# S206X.net
KiCad netlist of a schematic drawn in EAGLE
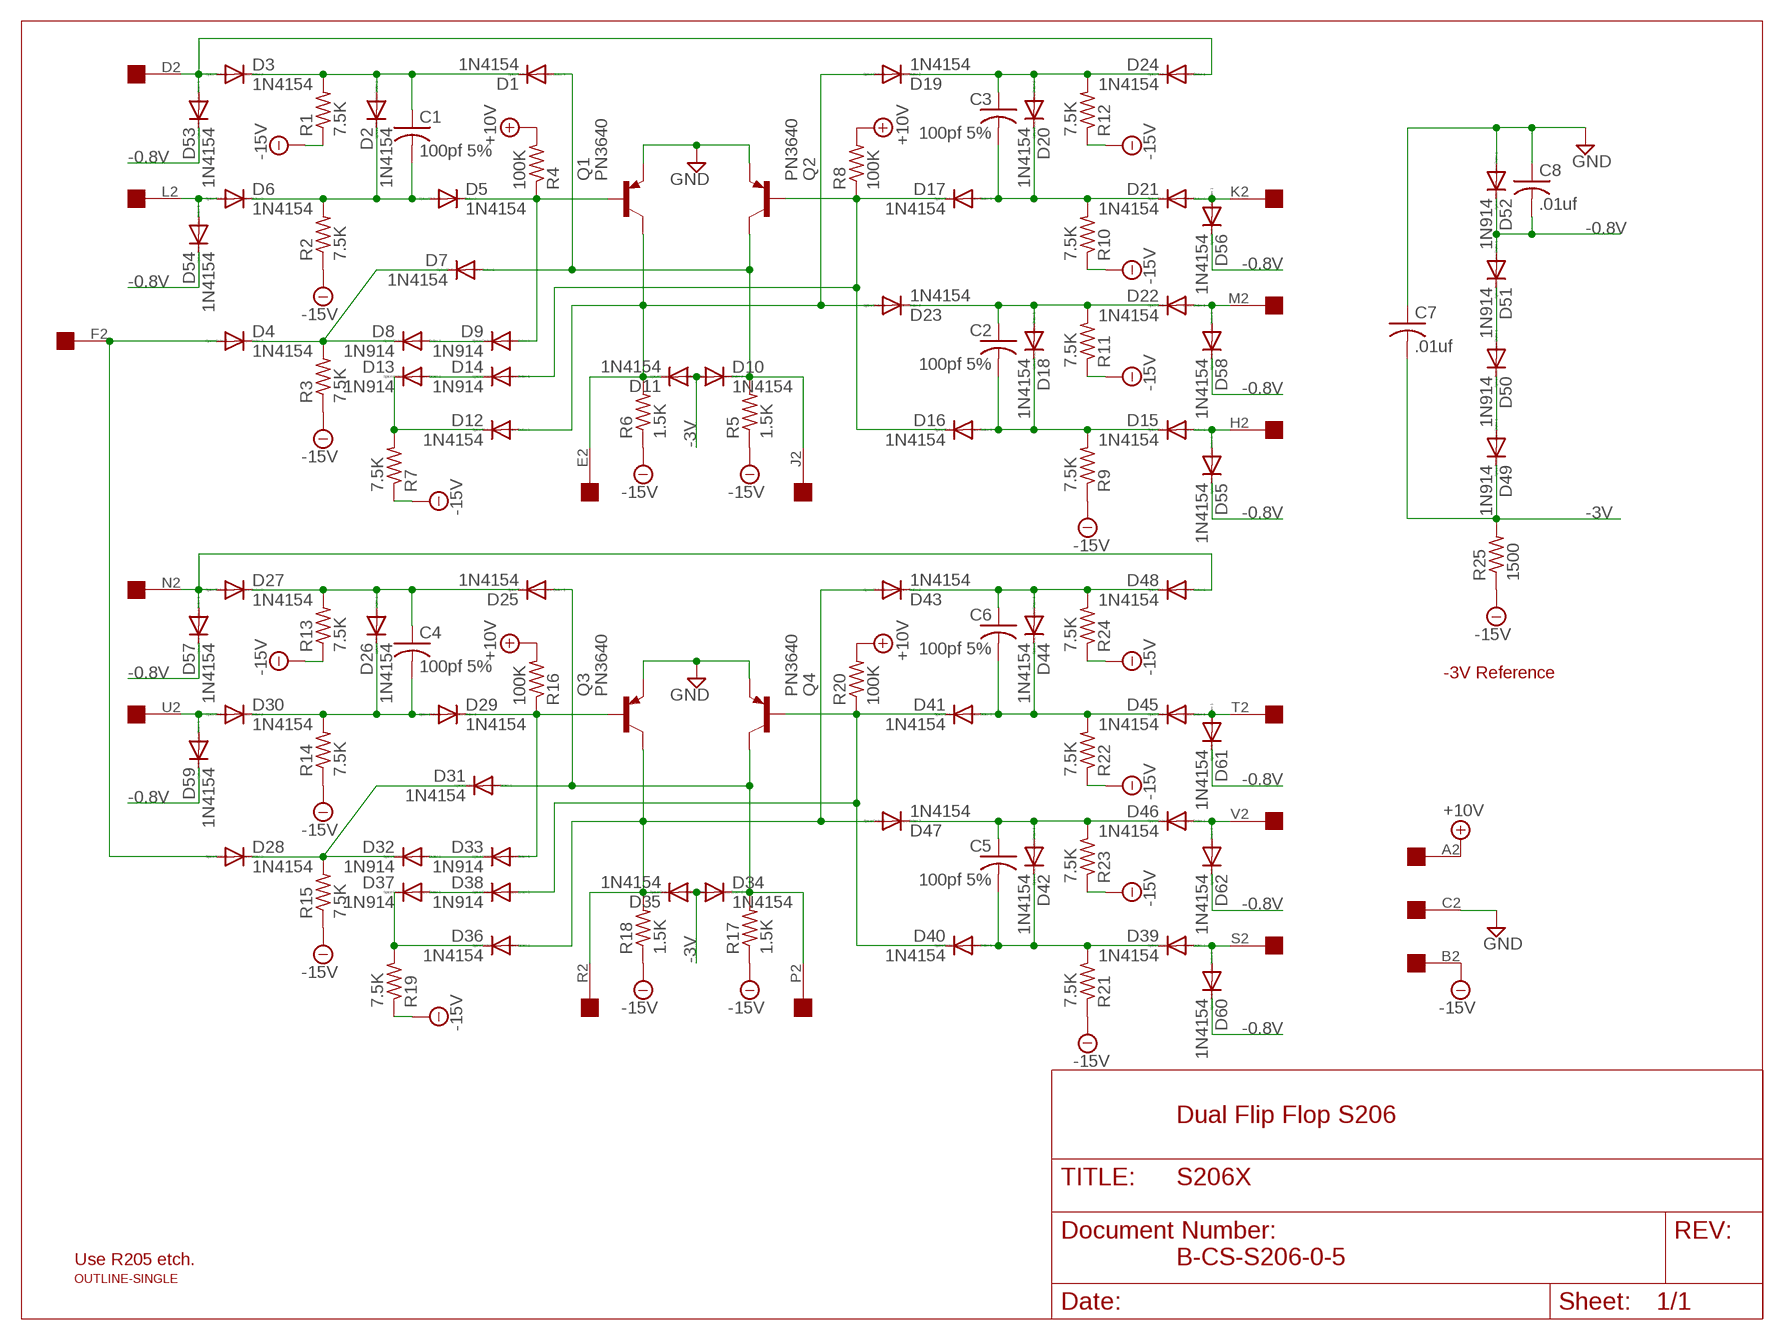
[diagram p0: schematic, sheet 1]

(export (version "E")
  (design (tool "Eeschema 10.0.6"))
  (components
    (comp (ref "C1")
      (value "100pf 5%")
      (footprint "eagle-import:C050-025X075")
      (libsource (lib "eagle-import") (part "C-US050-025X075"))
    )
    (comp (ref "C2")
      (value "100pf 5%")
      (footprint "eagle-import:C050-025X075")
      (libsource (lib "eagle-import") (part "C-US050-025X075"))
    )
    (comp (ref "C3")
      (value "100pf 5%")
      (footprint "eagle-import:C050-025X075")
      (libsource (lib "eagle-import") (part "C-US050-025X075"))
    )
    (comp (ref "C4")
      (value "100pf 5%")
      (footprint "eagle-import:C050-025X075")
      (libsource (lib "eagle-import") (part "C-US050-025X075"))
    )
    (comp (ref "C5")
      (value "100pf 5%")
      (footprint "eagle-import:C050-025X075")
      (libsource (lib "eagle-import") (part "C-US050-025X075"))
    )
    (comp (ref "C6")
      (value "100pf 5%")
      (footprint "eagle-import:C050-025X075")
      (libsource (lib "eagle-import") (part "C-US050-025X075"))
    )
    (comp (ref "C7")
      (value ".01uf")
      (footprint "eagle-import:C050-025X075")
      (libsource (lib "eagle-import") (part "C-US050-025X075"))
    )
    (comp (ref "C8")
      (value ".01uf")
      (footprint "eagle-import:C050-025X075")
      (libsource (lib "eagle-import") (part "C-US050-025X075"))
    )
    (comp (ref "D1")
      (value "1N4154")
      (footprint "eagle-import:DO35-10")
      (libsource (lib "eagle-import") (part "1N4148DO35-10"))
    )
    (comp (ref "D2")
      (value "1N4154")
      (footprint "eagle-import:DO35-10")
      (libsource (lib "eagle-import") (part "1N4148DO35-10"))
    )
    (comp (ref "D3")
      (value "1N4154")
      (footprint "eagle-import:DO35-10")
      (libsource (lib "eagle-import") (part "1N4148DO35-10"))
    )
    (comp (ref "D4")
      (value "1N4154")
      (footprint "eagle-import:DO35-10")
      (libsource (lib "eagle-import") (part "1N4148DO35-10"))
    )
    (comp (ref "D5")
      (value "1N4154")
      (footprint "eagle-import:DO35-10")
      (libsource (lib "eagle-import") (part "1N4148DO35-10"))
    )
    (comp (ref "D6")
      (value "1N4154")
      (footprint "eagle-import:DO35-10")
      (libsource (lib "eagle-import") (part "1N4148DO35-10"))
    )
    (comp (ref "D7")
      (value "1N4154")
      (footprint "eagle-import:DO35-10")
      (libsource (lib "eagle-import") (part "1N4148DO35-10"))
    )
    (comp (ref "D8")
      (value "1N914")
      (footprint "eagle-import:DO35-10")
      (libsource (lib "eagle-import") (part "1N4148DO35-10"))
    )
    (comp (ref "D9")
      (value "1N914")
      (footprint "eagle-import:DO35-10")
      (libsource (lib "eagle-import") (part "1N4148DO35-10"))
    )
    (comp (ref "D10")
      (value "1N4154")
      (footprint "eagle-import:DO35-10")
      (libsource (lib "eagle-import") (part "1N4148DO35-10"))
    )
    (comp (ref "D11")
      (value "1N4154")
      (footprint "eagle-import:DO35-10")
      (libsource (lib "eagle-import") (part "1N4148DO35-10"))
    )
    (comp (ref "D12")
      (value "1N4154")
      (footprint "eagle-import:DO35-10")
      (libsource (lib "eagle-import") (part "1N4148DO35-10"))
    )
    (comp (ref "D13")
      (value "1N914")
      (footprint "eagle-import:DO35-10")
      (libsource (lib "eagle-import") (part "1N4148DO35-10"))
    )
    (comp (ref "D14")
      (value "1N914")
      (footprint "eagle-import:DO35-10")
      (libsource (lib "eagle-import") (part "1N4148DO35-10"))
    )
    (comp (ref "D15")
      (value "1N4154")
      (footprint "eagle-import:DO35-10")
      (libsource (lib "eagle-import") (part "1N4148DO35-10"))
    )
    (comp (ref "D16")
      (value "1N4154")
      (footprint "eagle-import:DO35-10")
      (libsource (lib "eagle-import") (part "1N4148DO35-10"))
    )
    (comp (ref "D17")
      (value "1N4154")
      (footprint "eagle-import:DO35-10")
      (libsource (lib "eagle-import") (part "1N4148DO35-10"))
    )
    (comp (ref "D18")
      (value "1N4154")
      (footprint "eagle-import:DO35-10")
      (libsource (lib "eagle-import") (part "1N4148DO35-10"))
    )
    (comp (ref "D19")
      (value "1N4154")
      (footprint "eagle-import:DO35-10")
      (libsource (lib "eagle-import") (part "1N4148DO35-10"))
    )
    (comp (ref "D20")
      (value "1N4154")
      (footprint "eagle-import:DO35-10")
      (libsource (lib "eagle-import") (part "1N4148DO35-10"))
    )
    (comp (ref "D21")
      (value "1N4154")
      (footprint "eagle-import:DO35-10")
      (libsource (lib "eagle-import") (part "1N4148DO35-10"))
    )
    (comp (ref "D22")
      (value "1N4154")
      (footprint "eagle-import:DO35-10")
      (libsource (lib "eagle-import") (part "1N4148DO35-10"))
    )
    (comp (ref "D23")
      (value "1N4154")
      (footprint "eagle-import:DO35-10")
      (libsource (lib "eagle-import") (part "1N4148DO35-10"))
    )
    (comp (ref "D24")
      (value "1N4154")
      (footprint "eagle-import:DO35-10")
      (libsource (lib "eagle-import") (part "1N4148DO35-10"))
    )
    (comp (ref "D25")
      (value "1N4154")
      (footprint "eagle-import:DO35-10")
      (libsource (lib "eagle-import") (part "1N4148DO35-10"))
    )
    (comp (ref "D26")
      (value "1N4154")
      (footprint "eagle-import:DO35-10")
      (libsource (lib "eagle-import") (part "1N4148DO35-10"))
    )
    (comp (ref "D27")
      (value "1N4154")
      (footprint "eagle-import:DO35-10")
      (libsource (lib "eagle-import") (part "1N4148DO35-10"))
    )
    (comp (ref "D28")
      (value "1N4154")
      (footprint "eagle-import:DO35-10")
      (libsource (lib "eagle-import") (part "1N4148DO35-10"))
    )
    (comp (ref "D29")
      (value "1N4154")
      (footprint "eagle-import:DO35-10")
      (libsource (lib "eagle-import") (part "1N4148DO35-10"))
    )
    (comp (ref "D30")
      (value "1N4154")
      (footprint "eagle-import:DO35-10")
      (libsource (lib "eagle-import") (part "1N4148DO35-10"))
    )
    (comp (ref "D31")
      (value "1N4154")
      (footprint "eagle-import:DO35-10")
      (libsource (lib "eagle-import") (part "1N4148DO35-10"))
    )
    (comp (ref "D32")
      (value "1N914")
      (footprint "eagle-import:DO35-10")
      (libsource (lib "eagle-import") (part "1N4148DO35-10"))
    )
    (comp (ref "D33")
      (value "1N914")
      (footprint "eagle-import:DO35-10")
      (libsource (lib "eagle-import") (part "1N4148DO35-10"))
    )
    (comp (ref "D34")
      (value "1N4154")
      (footprint "eagle-import:DO35-10")
      (libsource (lib "eagle-import") (part "1N4148DO35-10"))
    )
    (comp (ref "D35")
      (value "1N4154")
      (footprint "eagle-import:DO35-10")
      (libsource (lib "eagle-import") (part "1N4148DO35-10"))
    )
    (comp (ref "D36")
      (value "1N4154")
      (footprint "eagle-import:DO35-10")
      (libsource (lib "eagle-import") (part "1N4148DO35-10"))
    )
    (comp (ref "D37")
      (value "1N914")
      (footprint "eagle-import:DO35-10")
      (libsource (lib "eagle-import") (part "1N4148DO35-10"))
    )
    (comp (ref "D38")
      (value "1N914")
      (footprint "eagle-import:DO35-10")
      (libsource (lib "eagle-import") (part "1N4148DO35-10"))
    )
    (comp (ref "D39")
      (value "1N4154")
      (footprint "eagle-import:DO35-10")
      (libsource (lib "eagle-import") (part "1N4148DO35-10"))
    )
    (comp (ref "D40")
      (value "1N4154")
      (footprint "eagle-import:DO35-10")
      (libsource (lib "eagle-import") (part "1N4148DO35-10"))
    )
    (comp (ref "D41")
      (value "1N4154")
      (footprint "eagle-import:DO35-10")
      (libsource (lib "eagle-import") (part "1N4148DO35-10"))
    )
    (comp (ref "D42")
      (value "1N4154")
      (footprint "eagle-import:DO35-10")
      (libsource (lib "eagle-import") (part "1N4148DO35-10"))
    )
    (comp (ref "D43")
      (value "1N4154")
      (footprint "eagle-import:DO35-10")
      (libsource (lib "eagle-import") (part "1N4148DO35-10"))
    )
    (comp (ref "D44")
      (value "1N4154")
      (footprint "eagle-import:DO35-10")
      (libsource (lib "eagle-import") (part "1N4148DO35-10"))
    )
    (comp (ref "D45")
      (value "1N4154")
      (footprint "eagle-import:DO35-10")
      (libsource (lib "eagle-import") (part "1N4148DO35-10"))
    )
    (comp (ref "D46")
      (value "1N4154")
      (footprint "eagle-import:DO35-10")
      (libsource (lib "eagle-import") (part "1N4148DO35-10"))
    )
    (comp (ref "D47")
      (value "1N4154")
      (footprint "eagle-import:DO35-10")
      (libsource (lib "eagle-import") (part "1N4148DO35-10"))
    )
    (comp (ref "D48")
      (value "1N4154")
      (footprint "eagle-import:DO35-10")
      (libsource (lib "eagle-import") (part "1N4148DO35-10"))
    )
    (comp (ref "D49")
      (value "1N914")
      (footprint "eagle-import:DO35-10")
      (libsource (lib "eagle-import") (part "1N4148DO35-10"))
    )
    (comp (ref "D50")
      (value "1N914")
      (footprint "eagle-import:DO35-10")
      (libsource (lib "eagle-import") (part "1N4148DO35-10"))
    )
    (comp (ref "D51")
      (value "1N914")
      (footprint "eagle-import:DO35-10")
      (libsource (lib "eagle-import") (part "1N4148DO35-10"))
    )
    (comp (ref "D52")
      (value "1N914")
      (footprint "eagle-import:DO35-10")
      (libsource (lib "eagle-import") (part "1N4148DO35-10"))
    )
    (comp (ref "D53")
      (value "1N4154")
      (footprint "eagle-import:DO35-10")
      (libsource (lib "eagle-import") (part "1N4148DO35-10"))
    )
    (comp (ref "D54")
      (value "1N4154")
      (footprint "eagle-import:DO35-10")
      (libsource (lib "eagle-import") (part "1N4148DO35-10"))
    )
    (comp (ref "D55")
      (value "1N4154")
      (footprint "eagle-import:DO35-10")
      (libsource (lib "eagle-import") (part "1N4148DO35-10"))
    )
    (comp (ref "D56")
      (value "1N4154")
      (footprint "eagle-import:DO35-10")
      (libsource (lib "eagle-import") (part "1N4148DO35-10"))
    )
    (comp (ref "D57")
      (value "1N4154")
      (footprint "eagle-import:DO35-10")
      (libsource (lib "eagle-import") (part "1N4148DO35-10"))
    )
    (comp (ref "D58")
      (value "1N4154")
      (footprint "eagle-import:DO35-10")
      (libsource (lib "eagle-import") (part "1N4148DO35-10"))
    )
    (comp (ref "D59")
      (value "1N4154")
      (footprint "eagle-import:DO35-10")
      (libsource (lib "eagle-import") (part "1N4148DO35-10"))
    )
    (comp (ref "D60")
      (value "1N4154")
      (footprint "eagle-import:DO35-10")
      (libsource (lib "eagle-import") (part "1N4148DO35-10"))
    )
    (comp (ref "D61")
      (value "1N4154")
      (footprint "eagle-import:DO35-10")
      (libsource (lib "eagle-import") (part "1N4148DO35-10"))
    )
    (comp (ref "D62")
      (value "1N4154")
      (footprint "eagle-import:DO35-10")
      (libsource (lib "eagle-import") (part "1N4148DO35-10"))
    )
    (comp (ref "Q1")
      (value "PN3640")
      (footprint "eagle-import:TO39")
      (libsource (lib "eagle-import") (part "2N3637"))
    )
    (comp (ref "Q2")
      (value "PN3640")
      (footprint "eagle-import:TO39")
      (libsource (lib "eagle-import") (part "2N3637"))
    )
    (comp (ref "Q3")
      (value "PN3640")
      (footprint "eagle-import:TO39")
      (libsource (lib "eagle-import") (part "2N3637"))
    )
    (comp (ref "Q4")
      (value "PN3640")
      (footprint "eagle-import:TO39")
      (libsource (lib "eagle-import") (part "2N3637"))
    )
    (comp (ref "R1")
      (value "7.5K")
      (footprint "eagle-import:0207_10")
      (libsource (lib "eagle-import") (part "R-US_0207/10"))
    )
    (comp (ref "R2")
      (value "7.5K")
      (footprint "eagle-import:0207_10")
      (libsource (lib "eagle-import") (part "R-US_0207/10"))
    )
    (comp (ref "R3")
      (value "7.5K")
      (footprint "eagle-import:0207_10")
      (libsource (lib "eagle-import") (part "R-US_0207/10"))
    )
    (comp (ref "R4")
      (value "100K")
      (footprint "eagle-import:0207_10")
      (libsource (lib "eagle-import") (part "R-US_0207/10"))
    )
    (comp (ref "R5")
      (value "1.5K")
      (footprint "eagle-import:0207_10")
      (libsource (lib "eagle-import") (part "R-US_0207/10"))
    )
    (comp (ref "R6")
      (value "1.5K")
      (footprint "eagle-import:0207_10")
      (libsource (lib "eagle-import") (part "R-US_0207/10"))
    )
    (comp (ref "R7")
      (value "7.5K")
      (footprint "eagle-import:0207_10")
      (libsource (lib "eagle-import") (part "R-US_0207/10"))
    )
    (comp (ref "R8")
      (value "100K")
      (footprint "eagle-import:0207_10")
      (libsource (lib "eagle-import") (part "R-US_0207/10"))
    )
    (comp (ref "R9")
      (value "7.5K")
      (footprint "eagle-import:0207_10")
      (libsource (lib "eagle-import") (part "R-US_0207/10"))
    )
    (comp (ref "R10")
      (value "7.5K")
      (footprint "eagle-import:0207_10")
      (libsource (lib "eagle-import") (part "R-US_0207/10"))
    )
    (comp (ref "R11")
      (value "7.5K")
      (footprint "eagle-import:0207_10")
      (libsource (lib "eagle-import") (part "R-US_0207/10"))
    )
    (comp (ref "R12")
      (value "7.5K")
      (footprint "eagle-import:0207_10")
      (libsource (lib "eagle-import") (part "R-US_0207/10"))
    )
    (comp (ref "R13")
      (value "7.5K")
      (footprint "eagle-import:0207_10")
      (libsource (lib "eagle-import") (part "R-US_0207/10"))
    )
    (comp (ref "R14")
      (value "7.5K")
      (footprint "eagle-import:0207_10")
      (libsource (lib "eagle-import") (part "R-US_0207/10"))
    )
    (comp (ref "R15")
      (value "7.5K")
      (footprint "eagle-import:0207_10")
      (libsource (lib "eagle-import") (part "R-US_0207/10"))
    )
    (comp (ref "R16")
      (value "100K")
      (footprint "eagle-import:0207_10")
      (libsource (lib "eagle-import") (part "R-US_0207/10"))
    )
    (comp (ref "R17")
      (value "1.5K")
      (footprint "eagle-import:0207_10")
      (libsource (lib "eagle-import") (part "R-US_0207/10"))
    )
    (comp (ref "R18")
      (value "1.5K")
      (footprint "eagle-import:0207_10")
      (libsource (lib "eagle-import") (part "R-US_0207/10"))
    )
    (comp (ref "R19")
      (value "7.5K")
      (footprint "eagle-import:0207_10")
      (libsource (lib "eagle-import") (part "R-US_0207/10"))
    )
    (comp (ref "R20")
      (value "100K")
      (footprint "eagle-import:0207_10")
      (libsource (lib "eagle-import") (part "R-US_0207/10"))
    )
    (comp (ref "R21")
      (value "7.5K")
      (footprint "eagle-import:0207_10")
      (libsource (lib "eagle-import") (part "R-US_0207/10"))
    )
    (comp (ref "R22")
      (value "7.5K")
      (footprint "eagle-import:0207_10")
      (libsource (lib "eagle-import") (part "R-US_0207/10"))
    )
    (comp (ref "R23")
      (value "7.5K")
      (footprint "eagle-import:0207_10")
      (libsource (lib "eagle-import") (part "R-US_0207/10"))
    )
    (comp (ref "R24")
      (value "7.5K")
      (footprint "eagle-import:0207_10")
      (libsource (lib "eagle-import") (part "R-US_0207/10"))
    )
    (comp (ref "R25")
      (value "1500")
      (footprint "eagle-import:0207_10")
      (libsource (lib "eagle-import") (part "R-US_0207/10"))
    )
    (comp (ref "U$1")
      (value "OUTLINE-SINGLE")
      (footprint "eagle-import:SINGLE")
      (libsource (lib "eagle-import") (part "OUTLINE-SINGLE"))
    )
    (comp (ref "U$2")
      (value "EDGE-1")
      (footprint "eagle-import:EDGE-CON1")
      (libsource (lib "eagle-import") (part "EDGE-1"))
    )
  )
  (nets
    (net (code "1") (name "+10V") (class "Default")
      (node (ref "R16") (pin "2") (pinfunction "2_2") (pintype "passive"))
      (node (ref "R20") (pin "2") (pinfunction "2_2") (pintype "passive"))
      (node (ref "R4") (pin "2") (pinfunction "2_2") (pintype "passive"))
      (node (ref "R8") (pin "2") (pinfunction "2_2") (pintype "passive"))
      (node (ref "U$2") (pin "A2") (pinfunction "1_A2") (pintype "bidirectional"))
    )
    (net (code "2") (name "-15V") (class "Default")
      (node (ref "R1") (pin "1") (pinfunction "1_1") (pintype "passive"))
      (node (ref "R10") (pin "1") (pinfunction "1_1") (pintype "passive"))
      (node (ref "R11") (pin "1") (pinfunction "1_1") (pintype "passive"))
      (node (ref "R12") (pin "1") (pinfunction "1_1") (pintype "passive"))
      (node (ref "R13") (pin "1") (pinfunction "1_1") (pintype "passive"))
      (node (ref "R14") (pin "1") (pinfunction "1_1") (pintype "passive"))
      (node (ref "R15") (pin "1") (pinfunction "1_1") (pintype "passive"))
      (node (ref "R17") (pin "1") (pinfunction "1_1") (pintype "passive"))
      (node (ref "R18") (pin "1") (pinfunction "1_1") (pintype "passive"))
      (node (ref "R19") (pin "1") (pinfunction "1_1") (pintype "passive"))
      (node (ref "R2") (pin "1") (pinfunction "1_1") (pintype "passive"))
      (node (ref "R21") (pin "1") (pinfunction "1_1") (pintype "passive"))
      (node (ref "R22") (pin "1") (pinfunction "1_1") (pintype "passive"))
      (node (ref "R23") (pin "1") (pinfunction "1_1") (pintype "passive"))
      (node (ref "R24") (pin "1") (pinfunction "1_1") (pintype "passive"))
      (node (ref "R25") (pin "1") (pinfunction "1_1") (pintype "passive"))
      (node (ref "R3") (pin "1") (pinfunction "1_1") (pintype "passive"))
      (node (ref "R5") (pin "1") (pinfunction "1_1") (pintype "passive"))
      (node (ref "R6") (pin "1") (pinfunction "1_1") (pintype "passive"))
      (node (ref "R7") (pin "1") (pinfunction "1_1") (pintype "passive"))
      (node (ref "R9") (pin "1") (pinfunction "1_1") (pintype "passive"))
      (node (ref "U$2") (pin "B2") (pinfunction "1_B2") (pintype "bidirectional"))
    )
    (net (code "3") (name "/-0.8V") (class "Default")
      (node (ref "C8") (pin "2") (pinfunction "2_2") (pintype "passive"))
      (node (ref "D51") (pin "A") (pinfunction "A_A") (pintype "passive"))
      (node (ref "D52") (pin "C") (pinfunction "C_C") (pintype "passive"))
      (node (ref "D53") (pin "C") (pinfunction "C_C") (pintype "passive"))
      (node (ref "D54") (pin "C") (pinfunction "C_C") (pintype "passive"))
      (node (ref "D55") (pin "C") (pinfunction "C_C") (pintype "passive"))
      (node (ref "D56") (pin "C") (pinfunction "C_C") (pintype "passive"))
      (node (ref "D57") (pin "C") (pinfunction "C_C") (pintype "passive"))
      (node (ref "D58") (pin "C") (pinfunction "C_C") (pintype "passive"))
      (node (ref "D59") (pin "C") (pinfunction "C_C") (pintype "passive"))
      (node (ref "D60") (pin "C") (pinfunction "C_C") (pintype "passive"))
      (node (ref "D61") (pin "C") (pinfunction "C_C") (pintype "passive"))
      (node (ref "D62") (pin "C") (pinfunction "C_C") (pintype "passive"))
    )
    (net (code "4") (name "/-3V") (class "Default")
      (node (ref "C7") (pin "2") (pinfunction "2_2") (pintype "passive"))
      (node (ref "D10") (pin "A") (pinfunction "A_A") (pintype "passive"))
      (node (ref "D11") (pin "A") (pinfunction "A_A") (pintype "passive"))
      (node (ref "D34") (pin "A") (pinfunction "A_A") (pintype "passive"))
      (node (ref "D35") (pin "A") (pinfunction "A_A") (pintype "passive"))
      (node (ref "D49") (pin "C") (pinfunction "C_C") (pintype "passive"))
      (node (ref "R25") (pin "2") (pinfunction "2_2") (pintype "passive"))
    )
    (net (code "5") (name "GND") (class "Default")
      (node (ref "C7") (pin "1") (pinfunction "1_1") (pintype "passive"))
      (node (ref "C8") (pin "1") (pinfunction "1_1") (pintype "passive"))
      (node (ref "D52") (pin "A") (pinfunction "A_A") (pintype "passive"))
      (node (ref "Q1") (pin "1") (pinfunction "E_1") (pintype "passive"))
      (node (ref "Q2") (pin "1") (pinfunction "E_1") (pintype "passive"))
      (node (ref "Q3") (pin "1") (pinfunction "E_1") (pintype "passive"))
      (node (ref "Q4") (pin "1") (pinfunction "E_1") (pintype "passive"))
      (node (ref "U$2") (pin "C2") (pinfunction "1_C2") (pintype "bidirectional"))
    )
    (net (code "6") (name "Net-(C1-Pad1)") (class "Default")
      (node (ref "C1") (pin "1") (pinfunction "1_1") (pintype "passive"))
      (node (ref "D1") (pin "C") (pinfunction "C_C") (pintype "passive"))
      (node (ref "D2") (pin "A") (pinfunction "A_A") (pintype "passive"))
      (node (ref "D3") (pin "C") (pinfunction "C_C") (pintype "passive"))
      (node (ref "R1") (pin "2") (pinfunction "2_2") (pintype "passive"))
    )
    (net (code "7") (name "Net-(C1-Pad2)") (class "Default")
      (node (ref "C1") (pin "2") (pinfunction "2_2") (pintype "passive"))
      (node (ref "D2") (pin "C") (pinfunction "C_C") (pintype "passive"))
      (node (ref "D5") (pin "A") (pinfunction "A_A") (pintype "passive"))
      (node (ref "D6") (pin "C") (pinfunction "C_C") (pintype "passive"))
      (node (ref "R2") (pin "2") (pinfunction "2_2") (pintype "passive"))
    )
    (net (code "8") (name "Net-(C2-Pad1)") (class "Default")
      (node (ref "C2") (pin "1") (pinfunction "1_1") (pintype "passive"))
      (node (ref "D18") (pin "A") (pinfunction "A_A") (pintype "passive"))
      (node (ref "D22") (pin "C") (pinfunction "C_C") (pintype "passive"))
      (node (ref "D23") (pin "C") (pinfunction "C_C") (pintype "passive"))
      (node (ref "R11") (pin "2") (pinfunction "2_2") (pintype "passive"))
    )
    (net (code "9") (name "Net-(C2-Pad2)") (class "Default")
      (node (ref "C2") (pin "2") (pinfunction "2_2") (pintype "passive"))
      (node (ref "D15") (pin "C") (pinfunction "C_C") (pintype "passive"))
      (node (ref "D16") (pin "A") (pinfunction "A_A") (pintype "passive"))
      (node (ref "D18") (pin "C") (pinfunction "C_C") (pintype "passive"))
      (node (ref "R9") (pin "2") (pinfunction "2_2") (pintype "passive"))
    )
    (net (code "10") (name "Net-(C3-Pad1)") (class "Default")
      (node (ref "C3") (pin "1") (pinfunction "1_1") (pintype "passive"))
      (node (ref "D19") (pin "C") (pinfunction "C_C") (pintype "passive"))
      (node (ref "D20") (pin "A") (pinfunction "A_A") (pintype "passive"))
      (node (ref "D24") (pin "C") (pinfunction "C_C") (pintype "passive"))
      (node (ref "R12") (pin "2") (pinfunction "2_2") (pintype "passive"))
    )
    (net (code "11") (name "Net-(C3-Pad2)") (class "Default")
      (node (ref "C3") (pin "2") (pinfunction "2_2") (pintype "passive"))
      (node (ref "D17") (pin "A") (pinfunction "A_A") (pintype "passive"))
      (node (ref "D20") (pin "C") (pinfunction "C_C") (pintype "passive"))
      (node (ref "D21") (pin "C") (pinfunction "C_C") (pintype "passive"))
      (node (ref "R10") (pin "2") (pinfunction "2_2") (pintype "passive"))
    )
    (net (code "12") (name "Net-(C4-Pad1)") (class "Default")
      (node (ref "C4") (pin "1") (pinfunction "1_1") (pintype "passive"))
      (node (ref "D25") (pin "C") (pinfunction "C_C") (pintype "passive"))
      (node (ref "D26") (pin "A") (pinfunction "A_A") (pintype "passive"))
      (node (ref "D27") (pin "C") (pinfunction "C_C") (pintype "passive"))
      (node (ref "R13") (pin "2") (pinfunction "2_2") (pintype "passive"))
    )
    (net (code "13") (name "Net-(C4-Pad2)") (class "Default")
      (node (ref "C4") (pin "2") (pinfunction "2_2") (pintype "passive"))
      (node (ref "D26") (pin "C") (pinfunction "C_C") (pintype "passive"))
      (node (ref "D29") (pin "A") (pinfunction "A_A") (pintype "passive"))
      (node (ref "D30") (pin "C") (pinfunction "C_C") (pintype "passive"))
      (node (ref "R14") (pin "2") (pinfunction "2_2") (pintype "passive"))
    )
    (net (code "14") (name "Net-(C5-Pad1)") (class "Default")
      (node (ref "C5") (pin "1") (pinfunction "1_1") (pintype "passive"))
      (node (ref "D42") (pin "A") (pinfunction "A_A") (pintype "passive"))
      (node (ref "D46") (pin "C") (pinfunction "C_C") (pintype "passive"))
      (node (ref "D47") (pin "C") (pinfunction "C_C") (pintype "passive"))
      (node (ref "R23") (pin "2") (pinfunction "2_2") (pintype "passive"))
    )
    (net (code "15") (name "Net-(C5-Pad2)") (class "Default")
      (node (ref "C5") (pin "2") (pinfunction "2_2") (pintype "passive"))
      (node (ref "D39") (pin "C") (pinfunction "C_C") (pintype "passive"))
      (node (ref "D40") (pin "A") (pinfunction "A_A") (pintype "passive"))
      (node (ref "D42") (pin "C") (pinfunction "C_C") (pintype "passive"))
      (node (ref "R21") (pin "2") (pinfunction "2_2") (pintype "passive"))
    )
    (net (code "16") (name "Net-(C6-Pad1)") (class "Default")
      (node (ref "C6") (pin "1") (pinfunction "1_1") (pintype "passive"))
      (node (ref "D43") (pin "C") (pinfunction "C_C") (pintype "passive"))
      (node (ref "D44") (pin "A") (pinfunction "A_A") (pintype "passive"))
      (node (ref "D48") (pin "C") (pinfunction "C_C") (pintype "passive"))
      (node (ref "R24") (pin "2") (pinfunction "2_2") (pintype "passive"))
    )
    (net (code "17") (name "Net-(C6-Pad2)") (class "Default")
      (node (ref "C6") (pin "2") (pinfunction "2_2") (pintype "passive"))
      (node (ref "D41") (pin "A") (pinfunction "A_A") (pintype "passive"))
      (node (ref "D44") (pin "C") (pinfunction "C_C") (pintype "passive"))
      (node (ref "D45") (pin "C") (pinfunction "C_C") (pintype "passive"))
      (node (ref "R22") (pin "2") (pinfunction "2_2") (pintype "passive"))
    )
    (net (code "18") (name "Net-(D4-PadC)") (class "Default")
      (node (ref "D4") (pin "C") (pinfunction "C_C") (pintype "passive"))
      (node (ref "D7") (pin "C") (pinfunction "C_C") (pintype "passive"))
      (node (ref "D8") (pin "C") (pinfunction "C_C") (pintype "passive"))
      (node (ref "R3") (pin "2") (pinfunction "2_2") (pintype "passive"))
    )
    (net (code "19") (name "Net-(D8-PadA)") (class "Default")
      (node (ref "D8") (pin "A") (pinfunction "A_A") (pintype "passive"))
      (node (ref "D9") (pin "C") (pinfunction "C_C") (pintype "passive"))
    )
    (net (code "20") (name "Net-(D12-PadC)") (class "Default")
      (node (ref "D12") (pin "C") (pinfunction "C_C") (pintype "passive"))
      (node (ref "D13") (pin "C") (pinfunction "C_C") (pintype "passive"))
      (node (ref "R7") (pin "2") (pinfunction "2_2") (pintype "passive"))
    )
    (net (code "21") (name "Net-(D13-PadA)") (class "Default")
      (node (ref "D13") (pin "A") (pinfunction "A_A") (pintype "passive"))
      (node (ref "D14") (pin "C") (pinfunction "C_C") (pintype "passive"))
    )
    (net (code "22") (name "Net-(D28-PadC)") (class "Default")
      (node (ref "D28") (pin "C") (pinfunction "C_C") (pintype "passive"))
      (node (ref "D31") (pin "C") (pinfunction "C_C") (pintype "passive"))
      (node (ref "D32") (pin "C") (pinfunction "C_C") (pintype "passive"))
      (node (ref "R15") (pin "2") (pinfunction "2_2") (pintype "passive"))
    )
    (net (code "23") (name "Net-(D32-PadA)") (class "Default")
      (node (ref "D32") (pin "A") (pinfunction "A_A") (pintype "passive"))
      (node (ref "D33") (pin "C") (pinfunction "C_C") (pintype "passive"))
    )
    (net (code "24") (name "Net-(D36-PadC)") (class "Default")
      (node (ref "D36") (pin "C") (pinfunction "C_C") (pintype "passive"))
      (node (ref "D37") (pin "C") (pinfunction "C_C") (pintype "passive"))
      (node (ref "R19") (pin "2") (pinfunction "2_2") (pintype "passive"))
    )
    (net (code "25") (name "Net-(D37-PadA)") (class "Default")
      (node (ref "D37") (pin "A") (pinfunction "A_A") (pintype "passive"))
      (node (ref "D38") (pin "C") (pinfunction "C_C") (pintype "passive"))
    )
    (net (code "26") (name "Net-(D49-PadA)") (class "Default")
      (node (ref "D49") (pin "A") (pinfunction "A_A") (pintype "passive"))
      (node (ref "D50") (pin "C") (pinfunction "C_C") (pintype "passive"))
    )
    (net (code "27") (name "Net-(D50-PadA)") (class "Default")
      (node (ref "D50") (pin "A") (pinfunction "A_A") (pintype "passive"))
      (node (ref "D51") (pin "C") (pinfunction "C_C") (pintype "passive"))
    )
    (net (code "28") (name "Net-(Q1-B)") (class "Default")
      (node (ref "D5") (pin "C") (pinfunction "C_C") (pintype "passive"))
      (node (ref "D9") (pin "A") (pinfunction "A_A") (pintype "passive"))
      (node (ref "Q1") (pin "2") (pinfunction "B_2") (pintype "passive"))
      (node (ref "R4") (pin "1") (pinfunction "1_1") (pintype "passive"))
    )
    (net (code "29") (name "Net-(Q1-C)") (class "Default")
      (node (ref "D11") (pin "C") (pinfunction "C_C") (pintype "passive"))
      (node (ref "D12") (pin "A") (pinfunction "A_A") (pintype "passive"))
      (node (ref "D19") (pin "A") (pinfunction "A_A") (pintype "passive"))
      (node (ref "D23") (pin "A") (pinfunction "A_A") (pintype "passive"))
      (node (ref "Q1") (pin "3") (pinfunction "C_3") (pintype "passive"))
      (node (ref "R6") (pin "2") (pinfunction "2_2") (pintype "passive"))
      (node (ref "U$2") (pin "E2") (pinfunction "1_E2") (pintype "bidirectional"))
    )
    (net (code "30") (name "Net-(Q2-B)") (class "Default")
      (node (ref "D14") (pin "A") (pinfunction "A_A") (pintype "passive"))
      (node (ref "D16") (pin "C") (pinfunction "C_C") (pintype "passive"))
      (node (ref "D17") (pin "C") (pinfunction "C_C") (pintype "passive"))
      (node (ref "Q2") (pin "2") (pinfunction "B_2") (pintype "passive"))
      (node (ref "R8") (pin "1") (pinfunction "1_1") (pintype "passive"))
    )
    (net (code "31") (name "Net-(Q2-C)") (class "Default")
      (node (ref "D1") (pin "A") (pinfunction "A_A") (pintype "passive"))
      (node (ref "D10") (pin "C") (pinfunction "C_C") (pintype "passive"))
      (node (ref "D7") (pin "A") (pinfunction "A_A") (pintype "passive"))
      (node (ref "Q2") (pin "3") (pinfunction "C_3") (pintype "passive"))
      (node (ref "R5") (pin "2") (pinfunction "2_2") (pintype "passive"))
      (node (ref "U$2") (pin "J2") (pinfunction "1_J2") (pintype "bidirectional"))
    )
    (net (code "32") (name "Net-(Q3-B)") (class "Default")
      (node (ref "D29") (pin "C") (pinfunction "C_C") (pintype "passive"))
      (node (ref "D33") (pin "A") (pinfunction "A_A") (pintype "passive"))
      (node (ref "Q3") (pin "2") (pinfunction "B_2") (pintype "passive"))
      (node (ref "R16") (pin "1") (pinfunction "1_1") (pintype "passive"))
    )
    (net (code "33") (name "Net-(Q3-C)") (class "Default")
      (node (ref "D35") (pin "C") (pinfunction "C_C") (pintype "passive"))
      (node (ref "D36") (pin "A") (pinfunction "A_A") (pintype "passive"))
      (node (ref "D43") (pin "A") (pinfunction "A_A") (pintype "passive"))
      (node (ref "D47") (pin "A") (pinfunction "A_A") (pintype "passive"))
      (node (ref "Q3") (pin "3") (pinfunction "C_3") (pintype "passive"))
      (node (ref "R18") (pin "2") (pinfunction "2_2") (pintype "passive"))
      (node (ref "U$2") (pin "R2") (pinfunction "1_R2") (pintype "bidirectional"))
    )
    (net (code "34") (name "Net-(Q4-B)") (class "Default")
      (node (ref "D38") (pin "A") (pinfunction "A_A") (pintype "passive"))
      (node (ref "D40") (pin "C") (pinfunction "C_C") (pintype "passive"))
      (node (ref "D41") (pin "C") (pinfunction "C_C") (pintype "passive"))
      (node (ref "Q4") (pin "2") (pinfunction "B_2") (pintype "passive"))
      (node (ref "R20") (pin "1") (pinfunction "1_1") (pintype "passive"))
    )
    (net (code "35") (name "Net-(Q4-C)") (class "Default")
      (node (ref "D25") (pin "A") (pinfunction "A_A") (pintype "passive"))
      (node (ref "D31") (pin "A") (pinfunction "A_A") (pintype "passive"))
      (node (ref "D34") (pin "C") (pinfunction "C_C") (pintype "passive"))
      (node (ref "Q4") (pin "3") (pinfunction "C_3") (pintype "passive"))
      (node (ref "R17") (pin "2") (pinfunction "2_2") (pintype "passive"))
      (node (ref "U$2") (pin "P2") (pinfunction "1_P2") (pintype "bidirectional"))
    )
    (net (code "36") (name "Net-(U$2D-1)") (class "Default")
      (node (ref "D24") (pin "A") (pinfunction "A_A") (pintype "passive"))
      (node (ref "D3") (pin "A") (pinfunction "A_A") (pintype "passive"))
      (node (ref "D53") (pin "A") (pinfunction "A_A") (pintype "passive"))
      (node (ref "U$2") (pin "D2") (pinfunction "1_D2") (pintype "bidirectional"))
    )
    (net (code "37") (name "Net-(U$2F-1)") (class "Default")
      (node (ref "D28") (pin "A") (pinfunction "A_A") (pintype "passive"))
      (node (ref "D4") (pin "A") (pinfunction "A_A") (pintype "passive"))
      (node (ref "U$2") (pin "F2") (pinfunction "1_F2") (pintype "bidirectional"))
    )
    (net (code "38") (name "Net-(U$2G-1)") (class "Default")
      (node (ref "D15") (pin "A") (pinfunction "A_A") (pintype "passive"))
      (node (ref "D55") (pin "A") (pinfunction "A_A") (pintype "passive"))
      (node (ref "U$2") (pin "H2") (pinfunction "1_H2") (pintype "bidirectional"))
    )
    (net (code "39") (name "Net-(U$2I-1)") (class "Default")
      (node (ref "D21") (pin "A") (pinfunction "A_A") (pintype "passive"))
      (node (ref "D56") (pin "A") (pinfunction "A_A") (pintype "passive"))
      (node (ref "U$2") (pin "K2") (pinfunction "1_K2") (pintype "bidirectional"))
    )
    (net (code "40") (name "Net-(U$2J-1)") (class "Default")
      (node (ref "D54") (pin "A") (pinfunction "A_A") (pintype "passive"))
      (node (ref "D6") (pin "A") (pinfunction "A_A") (pintype "passive"))
      (node (ref "U$2") (pin "L2") (pinfunction "1_L2") (pintype "bidirectional"))
    )
    (net (code "41") (name "Net-(U$2K-1)") (class "Default")
      (node (ref "D22") (pin "A") (pinfunction "A_A") (pintype "passive"))
      (node (ref "D58") (pin "A") (pinfunction "A_A") (pintype "passive"))
      (node (ref "U$2") (pin "M2") (pinfunction "1_M2") (pintype "bidirectional"))
    )
    (net (code "42") (name "Net-(U$2L-1)") (class "Default")
      (node (ref "D27") (pin "A") (pinfunction "A_A") (pintype "passive"))
      (node (ref "D48") (pin "A") (pinfunction "A_A") (pintype "passive"))
      (node (ref "D57") (pin "A") (pinfunction "A_A") (pintype "passive"))
      (node (ref "U$2") (pin "N2") (pinfunction "1_N2") (pintype "bidirectional"))
    )
    (net (code "43") (name "Net-(U$2O-1)") (class "Default")
      (node (ref "D39") (pin "A") (pinfunction "A_A") (pintype "passive"))
      (node (ref "D60") (pin "A") (pinfunction "A_A") (pintype "passive"))
      (node (ref "U$2") (pin "S2") (pinfunction "1_S2") (pintype "bidirectional"))
    )
    (net (code "44") (name "Net-(U$2P-1)") (class "Default")
      (node (ref "D45") (pin "A") (pinfunction "A_A") (pintype "passive"))
      (node (ref "D61") (pin "A") (pinfunction "A_A") (pintype "passive"))
      (node (ref "U$2") (pin "T2") (pinfunction "1_T2") (pintype "bidirectional"))
    )
    (net (code "45") (name "Net-(U$2Q-1)") (class "Default")
      (node (ref "D30") (pin "A") (pinfunction "A_A") (pintype "passive"))
      (node (ref "D59") (pin "A") (pinfunction "A_A") (pintype "passive"))
      (node (ref "U$2") (pin "U2") (pinfunction "1_U2") (pintype "bidirectional"))
    )
    (net (code "46") (name "Net-(U$2R-1)") (class "Default")
      (node (ref "D46") (pin "A") (pinfunction "A_A") (pintype "passive"))
      (node (ref "D62") (pin "A") (pinfunction "A_A") (pintype "passive"))
      (node (ref "U$2") (pin "V2") (pinfunction "1_V2") (pintype "bidirectional"))
    )
  )
)
